# buck_converters.net
KiCad netlist of a schematic drawn in EAGLE
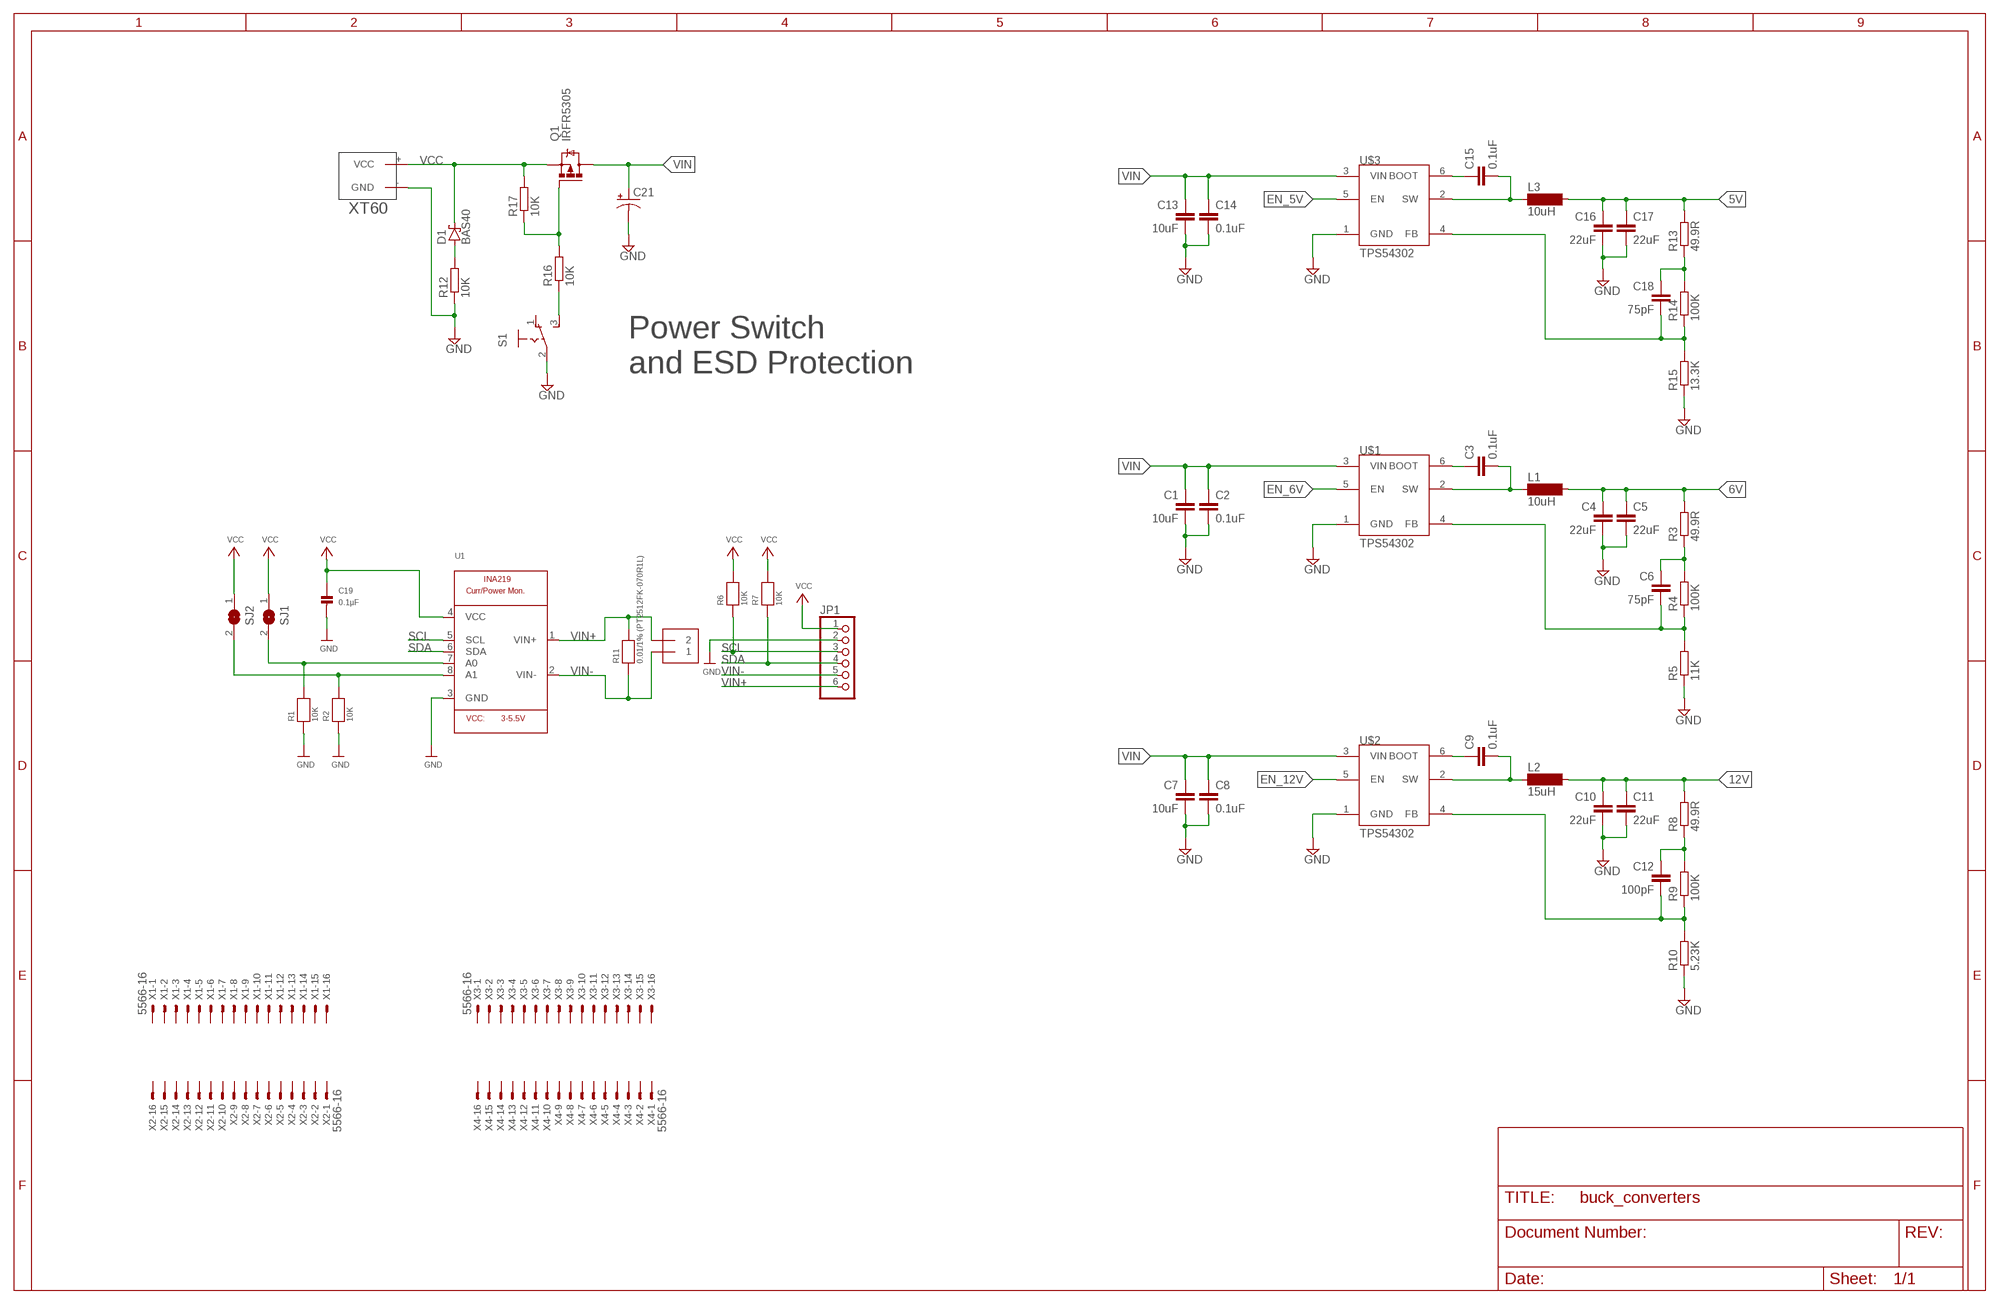
[diagram p0: schematic, sheet 1]

(export (version "E")
  (design (tool "Eeschema 10.0.6"))
  (components
    (comp (ref "C1")
      (value "10uF")
      (footprint "eagle-import:C0805")
      (libsource (lib "eagle-import") (part "C-EUC0805"))
    )
    (comp (ref "C2")
      (value "0.1uF")
      (footprint "eagle-import:C0805")
      (libsource (lib "eagle-import") (part "C-EUC0805"))
    )
    (comp (ref "C3")
      (value "0.1uF")
      (footprint "eagle-import:C0805")
      (libsource (lib "eagle-import") (part "C-EUC0805"))
    )
    (comp (ref "C4")
      (value "22uF")
      (footprint "eagle-import:C0805")
      (libsource (lib "eagle-import") (part "C-EUC0805"))
    )
    (comp (ref "C5")
      (value "22uF")
      (footprint "eagle-import:C0805")
      (libsource (lib "eagle-import") (part "C-EUC0805"))
    )
    (comp (ref "C6")
      (value "75pF")
      (footprint "eagle-import:C0805")
      (libsource (lib "eagle-import") (part "C-EUC0805"))
    )
    (comp (ref "C7")
      (value "10uF")
      (footprint "eagle-import:C0805")
      (libsource (lib "eagle-import") (part "C-EUC0805"))
    )
    (comp (ref "C8")
      (value "0.1uF")
      (footprint "eagle-import:C0805")
      (libsource (lib "eagle-import") (part "C-EUC0805"))
    )
    (comp (ref "C9")
      (value "0.1uF")
      (footprint "eagle-import:C0805")
      (libsource (lib "eagle-import") (part "C-EUC0805"))
    )
    (comp (ref "C10")
      (value "22uF")
      (footprint "eagle-import:C0805")
      (libsource (lib "eagle-import") (part "C-EUC0805"))
    )
    (comp (ref "C11")
      (value "22uF")
      (footprint "eagle-import:C0805")
      (libsource (lib "eagle-import") (part "C-EUC0805"))
    )
    (comp (ref "C12")
      (value "100pF")
      (footprint "eagle-import:C0805")
      (libsource (lib "eagle-import") (part "C-EUC0805"))
    )
    (comp (ref "C13")
      (value "10uF")
      (footprint "eagle-import:C0805")
      (libsource (lib "eagle-import") (part "C-EUC0805"))
    )
    (comp (ref "C14")
      (value "0.1uF")
      (footprint "eagle-import:C0805")
      (libsource (lib "eagle-import") (part "C-EUC0805"))
    )
    (comp (ref "C15")
      (value "0.1uF")
      (footprint "eagle-import:C0805")
      (libsource (lib "eagle-import") (part "C-EUC0805"))
    )
    (comp (ref "C16")
      (value "22uF")
      (footprint "eagle-import:C0805")
      (libsource (lib "eagle-import") (part "C-EUC0805"))
    )
    (comp (ref "C17")
      (value "22uF")
      (footprint "eagle-import:C0805")
      (libsource (lib "eagle-import") (part "C-EUC0805"))
    )
    (comp (ref "C18")
      (value "75pF")
      (footprint "eagle-import:C0805")
      (libsource (lib "eagle-import") (part "C-EUC0805"))
    )
    (comp (ref "C19")
      (value "0.1µF")
      (footprint "eagle-import:0805")
      (libsource (lib "eagle-import") (part "CAP_CERAMIC0805"))
    )
    (comp (ref "C21")
      (value "CPOL-US153CLV-1010")
      (footprint "eagle-import:153CLV-1010")
      (libsource (lib "eagle-import") (part "CPOL-US153CLV-1010"))
    )
    (comp (ref "D1")
      (value "BAS40")
      (footprint "eagle-import:SOT23")
      (libsource (lib "eagle-import") (part "BAS40"))
    )
    (comp (ref "J1")
      (value "TERMBLOCK_1X2-3.5MM")
      (footprint "eagle-import:1X2-3.5MM")
      (libsource (lib "eagle-import") (part "TERMBLOCK_1X2-3.5MM"))
    )
    (comp (ref "JP1")
      (value "HEADER-1X670MIL")
      (footprint "eagle-import:1X06_ROUND_70")
      (libsource (lib "eagle-import") (part "HEADER-1X670MIL"))
    )
    (comp (ref "L1")
      (value "10uH")
      (footprint "eagle-import:SM-NE29")
      (libsource (lib "eagle-import") (part "SM-NE29"))
    )
    (comp (ref "L2")
      (value "15uH")
      (footprint "eagle-import:SM-NE29")
      (libsource (lib "eagle-import") (part "SM-NE29"))
    )
    (comp (ref "L3")
      (value "10uH")
      (footprint "eagle-import:SM-NE29")
      (libsource (lib "eagle-import") (part "SM-NE29"))
    )
    (comp (ref "Q1")
      (value "IRFR5305")
      (footprint "eagle-import:D-PAK_TO252AA")
      (libsource (lib "eagle-import") (part "IRF?5305R"))
    )
    (comp (ref "R1")
      (value "10K")
      (footprint "eagle-import:0805")
      (libsource (lib "eagle-import") (part "RESISTOR0805"))
    )
    (comp (ref "R2")
      (value "10K")
      (footprint "eagle-import:0805")
      (libsource (lib "eagle-import") (part "RESISTOR0805"))
    )
    (comp (ref "R3")
      (value "49.9R")
      (footprint "eagle-import:R0805")
      (libsource (lib "eagle-import") (part "R-EU_R0805"))
    )
    (comp (ref "R4")
      (value "100K")
      (footprint "eagle-import:R0805")
      (libsource (lib "eagle-import") (part "R-EU_R0805"))
    )
    (comp (ref "R5")
      (value "11K")
      (footprint "eagle-import:R0805")
      (libsource (lib "eagle-import") (part "R-EU_R0805"))
    )
    (comp (ref "R6")
      (value "10K")
      (footprint "eagle-import:0805")
      (libsource (lib "eagle-import") (part "RESISTOR0805"))
    )
    (comp (ref "R7")
      (value "10K")
      (footprint "eagle-import:0805")
      (libsource (lib "eagle-import") (part "RESISTOR0805"))
    )
    (comp (ref "R8")
      (value "49.9R")
      (footprint "eagle-import:R0805")
      (libsource (lib "eagle-import") (part "R-EU_R0805"))
    )
    (comp (ref "R9")
      (value "100K")
      (footprint "eagle-import:R0805")
      (libsource (lib "eagle-import") (part "R-EU_R0805"))
    )
    (comp (ref "R10")
      (value "5.23K")
      (footprint "eagle-import:R0805")
      (libsource (lib "eagle-import") (part "R-EU_R0805"))
    )
    (comp (ref "R11")
      (value "0.01/1% (PT2512FK-070R1L)")
      (footprint "eagle-import:2512")
      (libsource (lib "eagle-import") (part "RESISTOR2512"))
    )
    (comp (ref "R12")
      (value "10K")
      (footprint "eagle-import:R0805")
      (libsource (lib "eagle-import") (part "R-EU_R0805"))
    )
    (comp (ref "R13")
      (value "49.9R")
      (footprint "eagle-import:R0805")
      (libsource (lib "eagle-import") (part "R-EU_R0805"))
    )
    (comp (ref "R14")
      (value "100K")
      (footprint "eagle-import:R0805")
      (libsource (lib "eagle-import") (part "R-EU_R0805"))
    )
    (comp (ref "R15")
      (value "13.3K")
      (footprint "eagle-import:R0805")
      (libsource (lib "eagle-import") (part "R-EU_R0805"))
    )
    (comp (ref "R16")
      (value "10K")
      (footprint "eagle-import:R0805")
      (libsource (lib "eagle-import") (part "R-EU_R0805"))
    )
    (comp (ref "R17")
      (value "10K")
      (footprint "eagle-import:R0805")
      (libsource (lib "eagle-import") (part "R-EU_R0805"))
    )
    (comp (ref "S1")
      (value "255SB")
      (footprint "eagle-import:255SB")
      (libsource (lib "eagle-import") (part "255SB"))
    )
    (comp (ref "SJ1")
      (value "SOLDERJUMPERREFLOW_NOPASTE")
      (footprint "eagle-import:SOLDERJUMPER_REFLOW_NOPASTE")
      (libsource (lib "eagle-import") (part "SOLDERJUMPERREFLOW_NOPASTE"))
    )
    (comp (ref "SJ2")
      (value "SOLDERJUMPERREFLOW_NOPASTE")
      (footprint "eagle-import:SOLDERJUMPER_REFLOW_NOPASTE")
      (libsource (lib "eagle-import") (part "SOLDERJUMPERREFLOW_NOPASTE"))
    )
    (comp (ref "U$1")
      (value "TPS54302")
      (footprint "eagle-import:SOT23-6")
      (libsource (lib "eagle-import") (part "TPS54302"))
    )
    (comp (ref "U$2")
      (value "TPS54302")
      (footprint "eagle-import:SOT23-6")
      (libsource (lib "eagle-import") (part "TPS54302"))
    )
    (comp (ref "U$3")
      (value "TPS54302")
      (footprint "eagle-import:SOT23-6")
      (libsource (lib "eagle-import") (part "TPS54302"))
    )
    (comp (ref "U$9")
      (value "XT60")
      (footprint "eagle-import:XT60")
      (libsource (lib "eagle-import") (part "XT60"))
    )
    (comp (ref "U1")
      (value "INA219")
      (footprint "eagle-import:SOT23-8")
      (libsource (lib "eagle-import") (part "INA219"))
    )
    (comp (ref "X1")
      (value "5566-16")
      (footprint "eagle-import:5566-16")
      (fields (field (name "MF") "MOLEX"))
      (libsource (lib "eagle-import") (part "5566-16"))
    )
    (comp (ref "X2")
      (value "5566-16")
      (footprint "eagle-import:5566-16")
      (fields (field (name "MF") "MOLEX"))
      (libsource (lib "eagle-import") (part "5566-16"))
    )
    (comp (ref "X3")
      (value "5566-16")
      (footprint "eagle-import:5566-16")
      (fields (field (name "MF") "MOLEX"))
      (libsource (lib "eagle-import") (part "5566-16"))
    )
    (comp (ref "X4")
      (value "5566-16")
      (footprint "eagle-import:5566-16")
      (fields (field (name "MF") "MOLEX"))
      (libsource (lib "eagle-import") (part "5566-16"))
    )
  )
  (nets
    (net (code "1") (name "/SCL") (class "Default")
      (node (ref "JP1") (pin "3") (pinfunction "3_3") (pintype "passive"))
      (node (ref "R6") (pin "1") (pinfunction "1_1") (pintype "passive"))
      (node (ref "U1") (pin "5") (pinfunction "SCL_5") (pintype "bidirectional"))
    )
    (net (code "2") (name "/SDA") (class "Default")
      (node (ref "JP1") (pin "4") (pinfunction "4_4") (pintype "passive"))
      (node (ref "R7") (pin "1") (pinfunction "1_1") (pintype "passive"))
      (node (ref "U1") (pin "6") (pinfunction "SDA_6") (pintype "bidirectional"))
    )
    (net (code "3") (name "/VIN+") (class "Default")
      (node (ref "J1") (pin "2") (pinfunction "2_2") (pintype "passive"))
      (node (ref "JP1") (pin "6") (pinfunction "6_6") (pintype "passive"))
      (node (ref "R11") (pin "2") (pinfunction "2_2") (pintype "passive"))
      (node (ref "U1") (pin "1") (pinfunction "VIN+_1") (pintype "bidirectional"))
    )
    (net (code "4") (name "/VIN-") (class "Default")
      (node (ref "J1") (pin "1") (pinfunction "1_1") (pintype "passive"))
      (node (ref "JP1") (pin "5") (pinfunction "5_5") (pintype "passive"))
      (node (ref "R11") (pin "1") (pinfunction "1_1") (pintype "passive"))
      (node (ref "U1") (pin "2") (pinfunction "VIN-_2") (pintype "bidirectional"))
    )
    (net (code "5") (name "5V") (class "Default")
      (node (ref "C16") (pin "1") (pinfunction "1_1") (pintype "passive"))
      (node (ref "C17") (pin "1") (pinfunction "1_1") (pintype "passive"))
      (node (ref "L3") (pin "2") (pinfunction "2_2") (pintype "passive"))
      (node (ref "R13") (pin "2") (pinfunction "2_2") (pintype "passive"))
    )
    (net (code "6") (name "6V") (class "Default")
      (node (ref "C4") (pin "1") (pinfunction "1_1") (pintype "passive"))
      (node (ref "C5") (pin "1") (pinfunction "1_1") (pintype "passive"))
      (node (ref "L1") (pin "2") (pinfunction "2_2") (pintype "passive"))
      (node (ref "R3") (pin "2") (pinfunction "2_2") (pintype "passive"))
    )
    (net (code "7") (name "12V") (class "Default")
      (node (ref "C10") (pin "1") (pinfunction "1_1") (pintype "passive"))
      (node (ref "C11") (pin "1") (pinfunction "1_1") (pintype "passive"))
      (node (ref "L2") (pin "2") (pinfunction "2_2") (pintype "passive"))
      (node (ref "R8") (pin "2") (pinfunction "2_2") (pintype "passive"))
    )
    (net (code "8") (name "EN_5V") (class "Default")
      (node (ref "U$3") (pin "5") (pinfunction "EN_5") (pintype "bidirectional"))
    )
    (net (code "9") (name "EN_6V") (class "Default")
      (node (ref "U$1") (pin "5") (pinfunction "EN_5") (pintype "bidirectional"))
    )
    (net (code "10") (name "EN_12V") (class "Default")
      (node (ref "U$2") (pin "5") (pinfunction "EN_5") (pintype "bidirectional"))
    )
    (net (code "11") (name "GND") (class "Default")
      (node (ref "C1") (pin "2") (pinfunction "2_2") (pintype "passive"))
      (node (ref "C10") (pin "2") (pinfunction "2_2") (pintype "passive"))
      (node (ref "C11") (pin "2") (pinfunction "2_2") (pintype "passive"))
      (node (ref "C13") (pin "2") (pinfunction "2_2") (pintype "passive"))
      (node (ref "C14") (pin "2") (pinfunction "2_2") (pintype "passive"))
      (node (ref "C16") (pin "2") (pinfunction "2_2") (pintype "passive"))
      (node (ref "C17") (pin "2") (pinfunction "2_2") (pintype "passive"))
      (node (ref "C19") (pin "2") (pinfunction "P$2_2") (pintype "passive"))
      (node (ref "C2") (pin "2") (pinfunction "2_2") (pintype "passive"))
      (node (ref "C21") (pin "-") (pinfunction "-_-") (pintype "passive"))
      (node (ref "C4") (pin "2") (pinfunction "2_2") (pintype "passive"))
      (node (ref "C5") (pin "2") (pinfunction "2_2") (pintype "passive"))
      (node (ref "C7") (pin "2") (pinfunction "2_2") (pintype "passive"))
      (node (ref "C8") (pin "2") (pinfunction "2_2") (pintype "passive"))
      (node (ref "JP1") (pin "2") (pinfunction "2_2") (pintype "passive"))
      (node (ref "R1") (pin "1") (pinfunction "1_1") (pintype "passive"))
      (node (ref "R10") (pin "1") (pinfunction "1_1") (pintype "passive"))
      (node (ref "R12") (pin "1") (pinfunction "1_1") (pintype "passive"))
      (node (ref "R15") (pin "1") (pinfunction "1_1") (pintype "passive"))
      (node (ref "R2") (pin "1") (pinfunction "1_1") (pintype "passive"))
      (node (ref "R5") (pin "1") (pinfunction "1_1") (pintype "passive"))
      (node (ref "S1") (pin "2") (pinfunction "P_2") (pintype "passive"))
      (node (ref "U$1") (pin "1") (pinfunction "GND_1") (pintype "bidirectional"))
      (node (ref "U$2") (pin "1") (pinfunction "GND_1") (pintype "bidirectional"))
      (node (ref "U$3") (pin "1") (pinfunction "GND_1") (pintype "bidirectional"))
      (node (ref "U$9") (pin "-") (pinfunction "GND_-") (pintype "bidirectional"))
      (node (ref "U1") (pin "3") (pinfunction "GND_3") (pintype "bidirectional"))
    )
    (net (code "12") (name "Net-(C6-Pad1)") (class "Default")
      (node (ref "C6") (pin "1") (pinfunction "1_1") (pintype "passive"))
      (node (ref "R3") (pin "1") (pinfunction "1_1") (pintype "passive"))
      (node (ref "R4") (pin "2") (pinfunction "2_2") (pintype "passive"))
    )
    (net (code "13") (name "Net-(C12-Pad1)") (class "Default")
      (node (ref "C12") (pin "1") (pinfunction "1_1") (pintype "passive"))
      (node (ref "R8") (pin "1") (pinfunction "1_1") (pintype "passive"))
      (node (ref "R9") (pin "2") (pinfunction "2_2") (pintype "passive"))
    )
    (net (code "14") (name "Net-(C18-Pad1)") (class "Default")
      (node (ref "C18") (pin "1") (pinfunction "1_1") (pintype "passive"))
      (node (ref "R13") (pin "1") (pinfunction "1_1") (pintype "passive"))
      (node (ref "R14") (pin "2") (pinfunction "2_2") (pintype "passive"))
    )
    (net (code "15") (name "Net-(D1-A)") (class "Default")
      (node (ref "D1") (pin "1") (pinfunction "A_1") (pintype "passive"))
      (node (ref "R12") (pin "2") (pinfunction "2_2") (pintype "passive"))
    )
    (net (code "16") (name "Net-(Q1-G)") (class "Default")
      (node (ref "Q1") (pin "1") (pinfunction "G_1") (pintype "passive"))
      (node (ref "R16") (pin "2") (pinfunction "2_2") (pintype "passive"))
      (node (ref "R17") (pin "1") (pinfunction "1_1") (pintype "passive"))
    )
    (net (code "17") (name "Net-(S1-S)") (class "Default")
      (node (ref "R16") (pin "1") (pinfunction "1_1") (pintype "passive"))
      (node (ref "S1") (pin "3") (pinfunction "S_3") (pintype "passive"))
    )
    (net (code "18") (name "Net-(U$1-BOOT)") (class "Default")
      (node (ref "C3") (pin "1") (pinfunction "1_1") (pintype "passive"))
      (node (ref "U$1") (pin "6") (pinfunction "BOOT_6") (pintype "bidirectional"))
    )
    (net (code "19") (name "Net-(U$1-FB)") (class "Default")
      (node (ref "C6") (pin "2") (pinfunction "2_2") (pintype "passive"))
      (node (ref "R4") (pin "1") (pinfunction "1_1") (pintype "passive"))
      (node (ref "R5") (pin "2") (pinfunction "2_2") (pintype "passive"))
      (node (ref "U$1") (pin "4") (pinfunction "FB_4") (pintype "bidirectional"))
    )
    (net (code "20") (name "Net-(U$1-SW)") (class "Default")
      (node (ref "C3") (pin "2") (pinfunction "2_2") (pintype "passive"))
      (node (ref "L1") (pin "1") (pinfunction "1_1") (pintype "passive"))
      (node (ref "U$1") (pin "2") (pinfunction "SW_2") (pintype "bidirectional"))
    )
    (net (code "21") (name "Net-(U$2-BOOT)") (class "Default")
      (node (ref "C9") (pin "1") (pinfunction "1_1") (pintype "passive"))
      (node (ref "U$2") (pin "6") (pinfunction "BOOT_6") (pintype "bidirectional"))
    )
    (net (code "22") (name "Net-(U$2-FB)") (class "Default")
      (node (ref "C12") (pin "2") (pinfunction "2_2") (pintype "passive"))
      (node (ref "R10") (pin "2") (pinfunction "2_2") (pintype "passive"))
      (node (ref "R9") (pin "1") (pinfunction "1_1") (pintype "passive"))
      (node (ref "U$2") (pin "4") (pinfunction "FB_4") (pintype "bidirectional"))
    )
    (net (code "23") (name "Net-(U$2-SW)") (class "Default")
      (node (ref "C9") (pin "2") (pinfunction "2_2") (pintype "passive"))
      (node (ref "L2") (pin "1") (pinfunction "1_1") (pintype "passive"))
      (node (ref "U$2") (pin "2") (pinfunction "SW_2") (pintype "bidirectional"))
    )
    (net (code "24") (name "Net-(U$3-BOOT)") (class "Default")
      (node (ref "C15") (pin "1") (pinfunction "1_1") (pintype "passive"))
      (node (ref "U$3") (pin "6") (pinfunction "BOOT_6") (pintype "bidirectional"))
    )
    (net (code "25") (name "Net-(U$3-FB)") (class "Default")
      (node (ref "C18") (pin "2") (pinfunction "2_2") (pintype "passive"))
      (node (ref "R14") (pin "1") (pinfunction "1_1") (pintype "passive"))
      (node (ref "R15") (pin "2") (pinfunction "2_2") (pintype "passive"))
      (node (ref "U$3") (pin "4") (pinfunction "FB_4") (pintype "bidirectional"))
    )
    (net (code "26") (name "Net-(U$3-SW)") (class "Default")
      (node (ref "C15") (pin "2") (pinfunction "2_2") (pintype "passive"))
      (node (ref "L3") (pin "1") (pinfunction "1_1") (pintype "passive"))
      (node (ref "U$3") (pin "2") (pinfunction "SW_2") (pintype "bidirectional"))
    )
    (net (code "27") (name "Net-(U1-A0)") (class "Default")
      (node (ref "R1") (pin "2") (pinfunction "2_2") (pintype "passive"))
      (node (ref "SJ1") (pin "2") (pinfunction "2_2") (pintype "passive"))
      (node (ref "U1") (pin "7") (pinfunction "A0_7") (pintype "bidirectional"))
    )
    (net (code "28") (name "Net-(U1-A1)") (class "Default")
      (node (ref "R2") (pin "2") (pinfunction "2_2") (pintype "passive"))
      (node (ref "SJ2") (pin "2") (pinfunction "2_2") (pintype "passive"))
      (node (ref "U1") (pin "8") (pinfunction "A1_8") (pintype "bidirectional"))
    )
    (net (code "29") (name "VCC") (class "Default")
      (node (ref "C19") (pin "1") (pinfunction "P$1_1") (pintype "passive"))
      (node (ref "D1") (pin "3") (pinfunction "C_3") (pintype "passive"))
      (node (ref "JP1") (pin "1") (pinfunction "1_1") (pintype "passive"))
      (node (ref "Q1") (pin "3") (pinfunction "S_3") (pintype "passive"))
      (node (ref "R17") (pin "2") (pinfunction "2_2") (pintype "passive"))
      (node (ref "R6") (pin "2") (pinfunction "2_2") (pintype "passive"))
      (node (ref "R7") (pin "2") (pinfunction "2_2") (pintype "passive"))
      (node (ref "SJ1") (pin "1") (pinfunction "1_1") (pintype "passive"))
      (node (ref "SJ2") (pin "1") (pinfunction "1_1") (pintype "passive"))
      (node (ref "U$9") (pin "+") (pinfunction "VCC_+") (pintype "bidirectional"))
      (node (ref "U1") (pin "4") (pinfunction "VCC_4") (pintype "bidirectional"))
    )
    (net (code "30") (name "VIN") (class "Default")
      (node (ref "C1") (pin "1") (pinfunction "1_1") (pintype "passive"))
      (node (ref "C13") (pin "1") (pinfunction "1_1") (pintype "passive"))
      (node (ref "C14") (pin "1") (pinfunction "1_1") (pintype "passive"))
      (node (ref "C2") (pin "1") (pinfunction "1_1") (pintype "passive"))
      (node (ref "C21") (pin "+") (pinfunction "+_+") (pintype "passive"))
      (node (ref "C7") (pin "1") (pinfunction "1_1") (pintype "passive"))
      (node (ref "C8") (pin "1") (pinfunction "1_1") (pintype "passive"))
      (node (ref "Q1") (pin "4") (pinfunction "D_4") (pintype "passive"))
      (node (ref "U$1") (pin "3") (pinfunction "VIN_3") (pintype "bidirectional"))
      (node (ref "U$2") (pin "3") (pinfunction "VIN_3") (pintype "bidirectional"))
      (node (ref "U$3") (pin "3") (pinfunction "VIN_3") (pintype "bidirectional"))
    )
    (net (code "31") (name "unconnected-(S1-O-Pad1)") (class "Default")
      (node (ref "S1") (pin "1") (pinfunction "O_1") (pintype "passive"))
    )
    (net (code "32") (name "unconnected-(X1A-S-Pad1)") (class "Default")
      (node (ref "X1") (pin "1") (pinfunction "S_1") (pintype "passive"))
    )
    (net (code "33") (name "unconnected-(X1B-S-Pad10)") (class "Default")
      (node (ref "X1") (pin "10") (pinfunction "S_10") (pintype "passive"))
    )
    (net (code "34") (name "unconnected-(X1C-S-Pad11)") (class "Default")
      (node (ref "X1") (pin "11") (pinfunction "S_11") (pintype "passive"))
    )
    (net (code "35") (name "unconnected-(X1D-S-Pad12)") (class "Default")
      (node (ref "X1") (pin "12") (pinfunction "S_12") (pintype "passive"))
    )
    (net (code "36") (name "unconnected-(X1E-S-Pad13)") (class "Default")
      (node (ref "X1") (pin "13") (pinfunction "S_13") (pintype "passive"))
    )
    (net (code "37") (name "unconnected-(X1F-S-Pad14)") (class "Default")
      (node (ref "X1") (pin "14") (pinfunction "S_14") (pintype "passive"))
    )
    (net (code "38") (name "unconnected-(X1G-S-Pad15)") (class "Default")
      (node (ref "X1") (pin "15") (pinfunction "S_15") (pintype "passive"))
    )
    (net (code "39") (name "unconnected-(X1H-S-Pad16)") (class "Default")
      (node (ref "X1") (pin "16") (pinfunction "S_16") (pintype "passive"))
    )
    (net (code "40") (name "unconnected-(X1I-S-Pad2)") (class "Default")
      (node (ref "X1") (pin "2") (pinfunction "S_2") (pintype "passive"))
    )
    (net (code "41") (name "unconnected-(X1J-S-Pad3)") (class "Default")
      (node (ref "X1") (pin "3") (pinfunction "S_3") (pintype "passive"))
    )
    (net (code "42") (name "unconnected-(X1K-S-Pad4)") (class "Default")
      (node (ref "X1") (pin "4") (pinfunction "S_4") (pintype "passive"))
    )
    (net (code "43") (name "unconnected-(X1L-S-Pad5)") (class "Default")
      (node (ref "X1") (pin "5") (pinfunction "S_5") (pintype "passive"))
    )
    (net (code "44") (name "unconnected-(X1M-S-Pad6)") (class "Default")
      (node (ref "X1") (pin "6") (pinfunction "S_6") (pintype "passive"))
    )
    (net (code "45") (name "unconnected-(X1N-S-Pad7)") (class "Default")
      (node (ref "X1") (pin "7") (pinfunction "S_7") (pintype "passive"))
    )
    (net (code "46") (name "unconnected-(X1O-S-Pad8)") (class "Default")
      (node (ref "X1") (pin "8") (pinfunction "S_8") (pintype "passive"))
    )
    (net (code "47") (name "unconnected-(X1P-S-Pad9)") (class "Default")
      (node (ref "X1") (pin "9") (pinfunction "S_9") (pintype "passive"))
    )
    (net (code "48") (name "unconnected-(X2A-S-Pad1)") (class "Default")
      (node (ref "X2") (pin "1") (pinfunction "S_1") (pintype "passive"))
    )
    (net (code "49") (name "unconnected-(X2B-S-Pad10)") (class "Default")
      (node (ref "X2") (pin "10") (pinfunction "S_10") (pintype "passive"))
    )
    (net (code "50") (name "unconnected-(X2C-S-Pad11)") (class "Default")
      (node (ref "X2") (pin "11") (pinfunction "S_11") (pintype "passive"))
    )
    (net (code "51") (name "unconnected-(X2D-S-Pad12)") (class "Default")
      (node (ref "X2") (pin "12") (pinfunction "S_12") (pintype "passive"))
    )
    (net (code "52") (name "unconnected-(X2E-S-Pad13)") (class "Default")
      (node (ref "X2") (pin "13") (pinfunction "S_13") (pintype "passive"))
    )
    (net (code "53") (name "unconnected-(X2F-S-Pad14)") (class "Default")
      (node (ref "X2") (pin "14") (pinfunction "S_14") (pintype "passive"))
    )
    (net (code "54") (name "unconnected-(X2G-S-Pad15)") (class "Default")
      (node (ref "X2") (pin "15") (pinfunction "S_15") (pintype "passive"))
    )
    (net (code "55") (name "unconnected-(X2H-S-Pad16)") (class "Default")
      (node (ref "X2") (pin "16") (pinfunction "S_16") (pintype "passive"))
    )
    (net (code "56") (name "unconnected-(X2I-S-Pad2)") (class "Default")
      (node (ref "X2") (pin "2") (pinfunction "S_2") (pintype "passive"))
    )
    (net (code "57") (name "unconnected-(X2J-S-Pad3)") (class "Default")
      (node (ref "X2") (pin "3") (pinfunction "S_3") (pintype "passive"))
    )
    (net (code "58") (name "unconnected-(X2K-S-Pad4)") (class "Default")
      (node (ref "X2") (pin "4") (pinfunction "S_4") (pintype "passive"))
    )
    (net (code "59") (name "unconnected-(X2L-S-Pad5)") (class "Default")
      (node (ref "X2") (pin "5") (pinfunction "S_5") (pintype "passive"))
    )
    (net (code "60") (name "unconnected-(X2M-S-Pad6)") (class "Default")
      (node (ref "X2") (pin "6") (pinfunction "S_6") (pintype "passive"))
    )
    (net (code "61") (name "unconnected-(X2N-S-Pad7)") (class "Default")
      (node (ref "X2") (pin "7") (pinfunction "S_7") (pintype "passive"))
    )
    (net (code "62") (name "unconnected-(X2O-S-Pad8)") (class "Default")
      (node (ref "X2") (pin "8") (pinfunction "S_8") (pintype "passive"))
    )
    (net (code "63") (name "unconnected-(X2P-S-Pad9)") (class "Default")
      (node (ref "X2") (pin "9") (pinfunction "S_9") (pintype "passive"))
    )
    (net (code "64") (name "unconnected-(X3A-S-Pad1)") (class "Default")
      (node (ref "X3") (pin "1") (pinfunction "S_1") (pintype "passive"))
    )
    (net (code "65") (name "unconnected-(X3B-S-Pad10)") (class "Default")
      (node (ref "X3") (pin "10") (pinfunction "S_10") (pintype "passive"))
    )
    (net (code "66") (name "unconnected-(X3C-S-Pad11)") (class "Default")
      (node (ref "X3") (pin "11") (pinfunction "S_11") (pintype "passive"))
    )
    (net (code "67") (name "unconnected-(X3D-S-Pad12)") (class "Default")
      (node (ref "X3") (pin "12") (pinfunction "S_12") (pintype "passive"))
    )
    (net (code "68") (name "unconnected-(X3E-S-Pad13)") (class "Default")
      (node (ref "X3") (pin "13") (pinfunction "S_13") (pintype "passive"))
    )
    (net (code "69") (name "unconnected-(X3F-S-Pad14)") (class "Default")
      (node (ref "X3") (pin "14") (pinfunction "S_14") (pintype "passive"))
    )
    (net (code "70") (name "unconnected-(X3G-S-Pad15)") (class "Default")
      (node (ref "X3") (pin "15") (pinfunction "S_15") (pintype "passive"))
    )
    (net (code "71") (name "unconnected-(X3H-S-Pad16)") (class "Default")
      (node (ref "X3") (pin "16") (pinfunction "S_16") (pintype "passive"))
    )
    (net (code "72") (name "unconnected-(X3I-S-Pad2)") (class "Default")
      (node (ref "X3") (pin "2") (pinfunction "S_2") (pintype "passive"))
    )
    (net (code "73") (name "unconnected-(X3J-S-Pad3)") (class "Default")
      (node (ref "X3") (pin "3") (pinfunction "S_3") (pintype "passive"))
    )
    (net (code "74") (name "unconnected-(X3K-S-Pad4)") (class "Default")
      (node (ref "X3") (pin "4") (pinfunction "S_4") (pintype "passive"))
    )
    (net (code "75") (name "unconnected-(X3L-S-Pad5)") (class "Default")
      (node (ref "X3") (pin "5") (pinfunction "S_5") (pintype "passive"))
    )
    (net (code "76") (name "unconnected-(X3M-S-Pad6)") (class "Default")
      (node (ref "X3") (pin "6") (pinfunction "S_6") (pintype "passive"))
    )
    (net (code "77") (name "unconnected-(X3N-S-Pad7)") (class "Default")
      (node (ref "X3") (pin "7") (pinfunction "S_7") (pintype "passive"))
    )
    (net (code "78") (name "unconnected-(X3O-S-Pad8)") (class "Default")
      (node (ref "X3") (pin "8") (pinfunction "S_8") (pintype "passive"))
    )
    (net (code "79") (name "unconnected-(X3P-S-Pad9)") (class "Default")
      (node (ref "X3") (pin "9") (pinfunction "S_9") (pintype "passive"))
    )
    (net (code "80") (name "unconnected-(X4A-S-Pad1)") (class "Default")
      (node (ref "X4") (pin "1") (pinfunction "S_1") (pintype "passive"))
    )
    (net (code "81") (name "unconnected-(X4B-S-Pad10)") (class "Default")
      (node (ref "X4") (pin "10") (pinfunction "S_10") (pintype "passive"))
    )
    (net (code "82") (name "unconnected-(X4C-S-Pad11)") (class "Default")
      (node (ref "X4") (pin "11") (pinfunction "S_11") (pintype "passive"))
    )
    (net (code "83") (name "unconnected-(X4D-S-Pad12)") (class "Default")
      (node (ref "X4") (pin "12") (pinfunction "S_12") (pintype "passive"))
    )
    (net (code "84") (name "unconnected-(X4E-S-Pad13)") (class "Default")
      (node (ref "X4") (pin "13") (pinfunction "S_13") (pintype "passive"))
    )
    (net (code "85") (name "unconnected-(X4F-S-Pad14)") (class "Default")
      (node (ref "X4") (pin "14") (pinfunction "S_14") (pintype "passive"))
    )
    (net (code "86") (name "unconnected-(X4G-S-Pad15)") (class "Default")
      (node (ref "X4") (pin "15") (pinfunction "S_15") (pintype "passive"))
    )
    (net (code "87") (name "unconnected-(X4H-S-Pad16)") (class "Default")
      (node (ref "X4") (pin "16") (pinfunction "S_16") (pintype "passive"))
    )
    (net (code "88") (name "unconnected-(X4I-S-Pad2)") (class "Default")
      (node (ref "X4") (pin "2") (pinfunction "S_2") (pintype "passive"))
    )
    (net (code "89") (name "unconnected-(X4J-S-Pad3)") (class "Default")
      (node (ref "X4") (pin "3") (pinfunction "S_3") (pintype "passive"))
    )
    (net (code "90") (name "unconnected-(X4K-S-Pad4)") (class "Default")
      (node (ref "X4") (pin "4") (pinfunction "S_4") (pintype "passive"))
    )
    (net (code "91") (name "unconnected-(X4L-S-Pad5)") (class "Default")
      (node (ref "X4") (pin "5") (pinfunction "S_5") (pintype "passive"))
    )
    (net (code "92") (name "unconnected-(X4M-S-Pad6)") (class "Default")
      (node (ref "X4") (pin "6") (pinfunction "S_6") (pintype "passive"))
    )
    (net (code "93") (name "unconnected-(X4N-S-Pad7)") (class "Default")
      (node (ref "X4") (pin "7") (pinfunction "S_7") (pintype "passive"))
    )
    (net (code "94") (name "unconnected-(X4O-S-Pad8)") (class "Default")
      (node (ref "X4") (pin "8") (pinfunction "S_8") (pintype "passive"))
    )
    (net (code "95") (name "unconnected-(X4P-S-Pad9)") (class "Default")
      (node (ref "X4") (pin "9") (pinfunction "S_9") (pintype "passive"))
    )
  )
)
